# RemoteSensors.net
KiCad netlist of a schematic drawn in Altium Designer
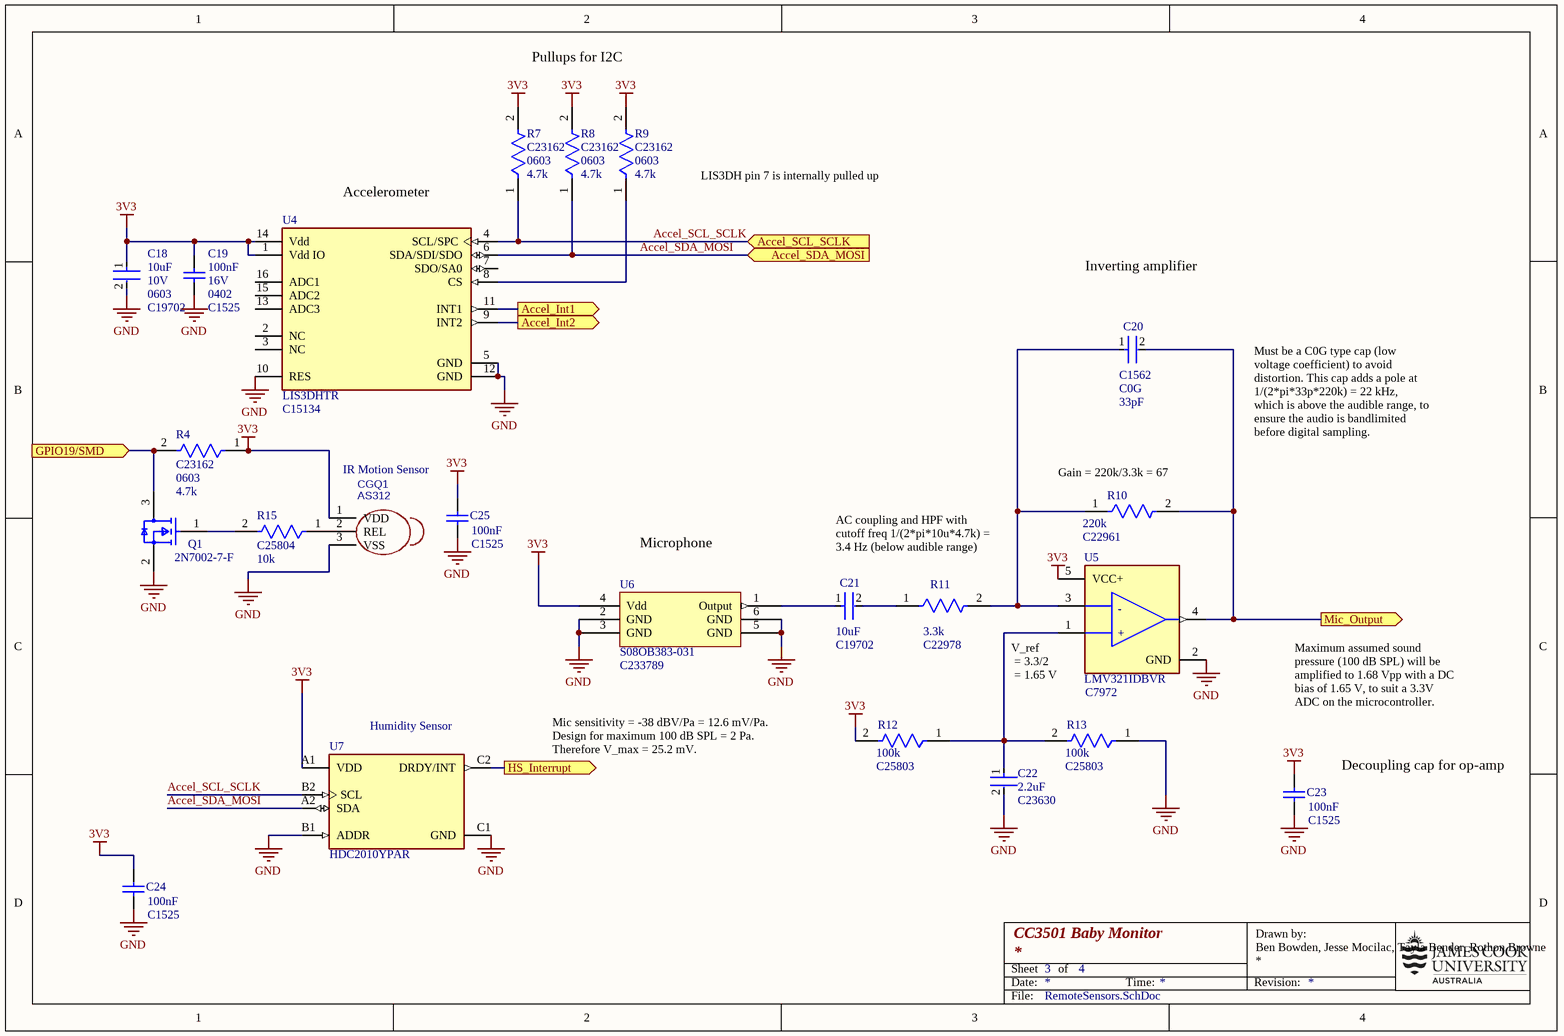
[diagram p0: RemoteSensors.SchDoc]

(export (version "E")
  (design (tool "Eeschema 10.0.6"))
  (components
    (comp (ref "C18")
      (value "CL10A106KP8NNNC")
      (footprint "FP-CL10-IPC_B")
      (description "Cap Ceramic 10uF 10V X5R ±10% Pad SMD 0603 +85°C T/R")
      (fields
        (field (name "TOLERANCE") "10%")
        (field (name "VOLTAGE RATING") "10V")
        (field (name "CASE CODE (IMPERIAL)") "0603")
        (field (name "JLCPCB PART") "C19702")
        (field (name "CAPACITANCE") "10uF")
      )
      (libsource (lib "James Cook University") (part "b4654b650e69147ec39a6b967a45e02"))
    )
    (comp (ref "C19")
      (value "CL05B104KO5NNNC")
      (footprint "CAPC1050X55X23ML05T13")
      (description "Chip Capacitor, 100 nF, +/- 10%, 16 V, -55 to 125 degC, 0402 (1005 Metric), RoHS, Tape and Reel")
      (fields
        (field (name "JLCPCB PART") "C1525")
        (field (name "CASE SIZE/DIMENSION") "0402")
        (field (name "CAPACITANCE") "100nF")
        (field (name "MANUFACTURER") "Samsung Electro-Mechanics")
        (field (name "RATED VOLTAGE") "16V")
      )
      (libsource (lib "James Cook University") (part "CAP-NP-2"))
    )
    (comp (ref "C20")
      (value "0402CG330J500NT")
      (footprint "FP-0402-L_1_0_1-W_0_5_0_1-IPC_A")
      (description "General Purpose Ceramic Capacitor, 0402, 33pF, 5%, C0G, 30ppm/°C, 50V")
      (fields
        (field (name "CAPACITANCE") "33pF")
        (field (name "DIELECTRIC") "C0G")
        (field (name "VOLTAGE") "50V")
        (field (name "JLCPCB PART") "C1562")
        (field (name "TOLERANCE") "5%")
      )
      (libsource (lib "James Cook University") (part "b4654b650e69147ec39a6b967a45e02"))
    )
    (comp (ref "C21")
      (value "CL10A106KP8NNNC")
      (footprint "FP-CL10-IPC_B")
      (description "Cap Ceramic 10uF 10V X5R ±10% Pad SMD 0603 +85°C T/R")
      (fields
        (field (name "JLCPCB PART") "C19702")
        (field (name "CAPACITANCE") "10uF")
        (field (name "TOLERANCE") "10%")
      )
      (libsource (lib "James Cook University") (part "b4654b650e69147ec39a6b967a45e02"))
    )
    (comp (ref "C22")
      (value "CL10A225KO8NNNC")
      (footprint "FP-CL10-IPC_B")
      (description "Cap Ceramic 2.2uF 16V X5R ±20% Pad SMD 0603 +85°C T/R")
      (fields
        (field (name "CAPACITANCE") "2.2uF")
        (field (name "TOLERANCE") "10%")
        (field (name "JLCPCB PART") "C23630")
      )
      (libsource (lib "James Cook University") (part "b4654b650e69147ec39a6b967a45e02"))
    )
    (comp (ref "C23")
      (value "CL05B104KO5NNNC")
      (footprint "CAPC1050X55X23ML05T13")
      (description "Chip Capacitor, 100 nF, +/- 10%, 16 V, -55 to 125 degC, 0402 (1005 Metric), RoHS, Tape and Reel")
      (fields
        (field (name "JLCPCB PART") "C1525")
        (field (name "CAPACITANCE") "100nF")
        (field (name "MANUFACTURER") "Samsung Electro-Mechanics")
      )
      (libsource (lib "James Cook University") (part "CAP-NP-2"))
    )
    (comp (ref "C24")
      (value "CL05B104KO5NNNC")
      (footprint "CAPC1050X55X23ML05T13")
      (description "Chip Capacitor, 100 nF, +/- 10%, 16 V, -55 to 125 degC, 0402 (1005 Metric), RoHS, Tape and Reel")
      (fields
        (field (name "JLCPCB PART") "C1525")
        (field (name "CAPACITANCE") "100nF")
        (field (name "MANUFACTURER") "Samsung Electro-Mechanics")
      )
      (libsource (lib "James Cook University") (part "CAP-NP-2"))
    )
    (comp (ref "C25")
      (value "CL05B104KO5NNNC")
      (footprint "CAPC1050X55X23ML05T13")
      (description "Chip Capacitor, 100 nF, +/- 10%, 16 V, -55 to 125 degC, 0402 (1005 Metric), RoHS, Tape and Reel")
      (fields
        (field (name "JLCPCB PART") "C1525")
        (field (name "CAPACITANCE") "100nF")
        (field (name "MANUFACTURER") "Samsung Electro-Mechanics")
      )
      (libsource (lib "James Cook University") (part "CAP-NP-2"))
    )
    (comp (ref "CGQ1")
      (value "AS312")
      (footprint "SENSORM-TH_3P_AS312")
      (fields (field (name "MANUFACTURER") "森霸"))
      (libsource (lib "altium-import") (part "root_0_AS312_"))
    )
    (comp (ref "Q1")
      (value "2N7002-7-F")
      (footprint "FP-SOT23-MFG")
      (description "MOSFET N-CH 60V 115MA SOT23-3")
      (fields (field (name "VOLTAGE") "60V"))
      (libsource (lib "Altium Content Vault") (part "3b9c635fedb024a5347a57b145af9cc"))
    )
    (comp (ref "R4")
      (value "0603WAF4701T5E")
      (footprint "FP-CRCW0603-e3-IPC_B")
      (description "RES Thick Film, 4.7kΩ, 1%, 0.1W, 100ppm/°C, 0603")
      (fields
        (field (name "JLCPCB PART") "C23162")
        (field (name "CASE/PACKAGE") "0603")
        (field (name "RESISTANCE") "4.7k")
        (field (name "TOLERANCE") "1%")
      )
      (libsource (lib "James Cook University") (part "1029c3af85768c4190bb7ad29bc67b5"))
    )
    (comp (ref "R7")
      (value "0603WAF4701T5E")
      (footprint "FP-CRCW0603-e3-IPC_B")
      (description "RES Thick Film, 4.7kΩ, 1%, 0.1W, 100ppm/°C, 0603")
      (fields
        (field (name "JLCPCB PART") "C23162")
        (field (name "CASE/PACKAGE") "0603")
        (field (name "RESISTANCE") "4.7k")
        (field (name "TOLERANCE") "1%")
      )
      (libsource (lib "James Cook University") (part "1029c3af85768c4190bb7ad29bc67b5"))
    )
    (comp (ref "R8")
      (value "0603WAF4701T5E")
      (footprint "FP-CRCW0603-e3-IPC_B")
      (description "RES Thick Film, 4.7kΩ, 1%, 0.1W, 100ppm/°C, 0603")
      (fields
        (field (name "JLCPCB PART") "C23162")
        (field (name "CASE/PACKAGE") "0603")
        (field (name "RESISTANCE") "4.7k")
        (field (name "TOLERANCE") "1%")
      )
      (libsource (lib "James Cook University") (part "1029c3af85768c4190bb7ad29bc67b5"))
    )
    (comp (ref "R9")
      (value "0603WAF4701T5E")
      (footprint "FP-CRCW0603-e3-IPC_B")
      (description "RES Thick Film, 4.7kΩ, 1%, 0.1W, 100ppm/°C, 0603")
      (fields
        (field (name "JLCPCB PART") "C23162")
        (field (name "CASE/PACKAGE") "0603")
        (field (name "RESISTANCE") "4.7k")
        (field (name "TOLERANCE") "1%")
      )
      (libsource (lib "James Cook University") (part "1029c3af85768c4190bb7ad29bc67b5"))
    )
    (comp (ref "R10")
      (value "0603WAF2203T5E")
      (footprint "FP-CRCW0603-e3-IPC_B")
      (description "RES Thick Film, 220kΩ, 1%, 0.1W, 100ppm/°C, 0603")
      (fields
        (field (name "RESISTANCE") "220k")
        (field (name "TOLERANCE") "1%")
        (field (name "JLCPCB PART") "C22961")
      )
      (libsource (lib "James Cook University") (part "1029c3af85768c4190bb7ad29bc67b5"))
    )
    (comp (ref "R11")
      (value "0603WAF3301T5E")
      (footprint "FP-CRCW0603-e3-IPC_B")
      (description "RES Thick Film, 3.3kΩ, 1%, 0.1W, 100ppm/°C, 0603")
      (fields
        (field (name "TOLERANCE") "1%")
        (field (name "JLCPCB PART") "C22978")
        (field (name "RESISTANCE") "3.3k")
      )
      (libsource (lib "James Cook University") (part "1029c3af85768c4190bb7ad29bc67b5"))
    )
    (comp (ref "R12")
      (value "0603WAF1003T5E")
      (footprint "FP-CRCW0603-e3-IPC_B")
      (description "RES Thick Film, 100kΩ, 1%, 0.1W, 100ppm/°C, 0603")
      (fields
        (field (name "JLCPCB PART") "C25803")
        (field (name "RESISTANCE") "100k")
        (field (name "TOLERANCE") "1%")
      )
      (libsource (lib "James Cook University") (part "1029c3af85768c4190bb7ad29bc67b5"))
    )
    (comp (ref "R13")
      (value "0603WAF1003T5E")
      (footprint "FP-CRCW0603-e3-IPC_B")
      (description "RES Thick Film, 100kΩ, 1%, 0.1W, 100ppm/°C, 0603")
      (fields
        (field (name "JLCPCB PART") "C25803")
        (field (name "RESISTANCE") "100k")
        (field (name "TOLERANCE") "1%")
      )
      (libsource (lib "James Cook University") (part "1029c3af85768c4190bb7ad29bc67b5"))
    )
    (comp (ref "R15")
      (value "0603WAF1002T5E")
      (footprint "FP-CRCW0603-e3-IPC_B")
      (description "RES Thick Film, 10kΩ, 1%, 0.1W, 100ppm/°C, 0603")
      (fields
        (field (name "TOLERANCE") "1%")
        (field (name "JLCPCB PART") "C25804")
        (field (name "RESISTANCE") "10k")
      )
      (libsource (lib "James Cook University") (part "1029c3af85768c4190bb7ad29bc67b5"))
    )
    (comp (ref "U4")
      (value "LIS3DHTR")
      (footprint "FP-LGA-16-7983231-MFG")
      (description "ACCEL 2-16G I2C/SPI 16LGA")
      (fields (field (name "JLCPCB PART") "C15134"))
      (libsource (lib "James Cook University") (part "1e4772b22d749da4b53766bc623c8dd"))
    )
    (comp (ref "U5")
      (value "LMV321IDBVR")
      (footprint "FP-DBV0005A-IPC_B")
      (description "General Purpose Amplifier 1 Circuit Rail-to-Rail SOT-23-5")
      (fields (field (name "JLCPCB PART") "C7972"))
      (libsource (lib "James Cook University") (part "ec165d7f6fd2c1e6935a66fb0025aed"))
    )
    (comp (ref "U6")
      (value "S08OB383-031")
      (footprint "Goertek_S08OB381-026")
      (description "MEMS Microphone SMD 3.76x3x1.1mm")
      (fields (field (name "JLCPCB PART") "C233789"))
      (libsource (lib "James Cook University") (part "Goertek S08OB381-026"))
    )
    (comp (ref "U7")
      (value "HDC2010YPAR")
      (footprint "FP-YPA0006-MFG")
      (description "GEN 2 HUMIDITY SENSOR")
      (fields
        (field (name "MANUFACTURER") "Texas Instruments")
        (field (name "OCTOPART") "https://octopart.com/hdc2010ypar-texas+instruments-84791680")
      )
      (libsource (lib "Altium Content Vault") (part "89629a78d3446019ed046f2f7a99f7b"))
    )
  )
  (nets
    (net (code "1") (name "/Accel_Int1") (class "Default")
      (node (ref "U4") (pin "11") (pinfunction "INT1_11") (pintype "output"))
    )
    (net (code "2") (name "/Accel_Int2") (class "Default")
      (node (ref "U4") (pin "9") (pinfunction "INT2_9") (pintype "output"))
    )
    (net (code "3") (name "/Accel_SCL_SCLK") (class "Default")
      (node (ref "R7") (pin "1") (pinfunction "1_1") (pintype "passive"))
      (node (ref "U4") (pin "4") (pinfunction "SCL/SPC_4") (pintype "input"))
      (node (ref "U7") (pin "B2") (pinfunction "SCL_B2") (pintype "input"))
    )
    (net (code "4") (name "/Accel_SDA_MOSI") (class "Default")
      (node (ref "R8") (pin "1") (pinfunction "1_1") (pintype "passive"))
      (node (ref "U4") (pin "6") (pinfunction "SDA/SDI/SDO_6") (pintype "bidirectional"))
      (node (ref "U7") (pin "A2") (pinfunction "SDA_A2") (pintype "bidirectional"))
    )
    (net (code "5") (name "/GPIO19{slash}SMD") (class "Default")
      (node (ref "Q1") (pin "3") (pinfunction "D_3") (pintype "passive"))
      (node (ref "R4") (pin "2") (pinfunction "2_2") (pintype "passive"))
    )
    (net (code "6") (name "/HS_Interrupt") (class "Default")
      (node (ref "U7") (pin "C2") (pinfunction "DRDY/INT_C2") (pintype "output"))
    )
    (net (code "7") (name "/Mic_Output") (class "Default")
      (node (ref "C20") (pin "2") (pinfunction "2_2") (pintype "passive"))
      (node (ref "R10") (pin "2") (pinfunction "2_2") (pintype "passive"))
      (node (ref "U5") (pin "4") (pinfunction "OUT_4") (pintype "output"))
    )
    (net (code "8") (name "3V3") (class "Default")
      (node (ref "C18") (pin "1") (pinfunction "1_1") (pintype "passive"))
      (node (ref "C19") (pin "2") (pinfunction "2_2") (pintype "passive"))
      (node (ref "C23") (pin "2") (pinfunction "2_2") (pintype "passive"))
      (node (ref "C24") (pin "2") (pinfunction "2_2") (pintype "passive"))
      (node (ref "C25") (pin "2") (pinfunction "2_2") (pintype "passive"))
      (node (ref "CGQ1") (pin "1") (pinfunction "VDD_1") (pintype "passive"))
      (node (ref "R12") (pin "2") (pinfunction "2_2") (pintype "passive"))
      (node (ref "R4") (pin "1") (pinfunction "1_1") (pintype "passive"))
      (node (ref "R7") (pin "2") (pinfunction "2_2") (pintype "passive"))
      (node (ref "R8") (pin "2") (pinfunction "2_2") (pintype "passive"))
      (node (ref "R9") (pin "2") (pinfunction "2_2") (pintype "passive"))
      (node (ref "U4") (pin "1") (pinfunction "Vdd_IO_1") (pintype "power_in"))
      (node (ref "U4") (pin "14") (pinfunction "Vdd_14") (pintype "power_in"))
      (node (ref "U5") (pin "5") (pinfunction "VCC+_5") (pintype "power_in"))
      (node (ref "U6") (pin "4") (pinfunction "Vdd_4") (pintype "power_in"))
      (node (ref "U7") (pin "A1") (pinfunction "VDD_A1") (pintype "power_in"))
    )
    (net (code "9") (name "GND") (class "Default")
      (node (ref "C18") (pin "2") (pinfunction "2_2") (pintype "passive"))
      (node (ref "C19") (pin "1") (pinfunction "1_1") (pintype "passive"))
      (node (ref "C22") (pin "2") (pinfunction "2_2") (pintype "passive"))
      (node (ref "C23") (pin "1") (pinfunction "1_1") (pintype "passive"))
      (node (ref "C24") (pin "1") (pinfunction "1_1") (pintype "passive"))
      (node (ref "C25") (pin "1") (pinfunction "1_1") (pintype "passive"))
      (node (ref "CGQ1") (pin "3") (pinfunction "VSS_3") (pintype "passive"))
      (node (ref "Q1") (pin "2") (pinfunction "S_2") (pintype "passive"))
      (node (ref "R13") (pin "1") (pinfunction "1_1") (pintype "passive"))
      (node (ref "U4") (pin "10") (pinfunction "RES_10") (pintype "passive"))
      (node (ref "U4") (pin "12") (pinfunction "GND_12") (pintype "power_in"))
      (node (ref "U4") (pin "5") (pinfunction "GND_5") (pintype "power_in"))
      (node (ref "U5") (pin "2") (pinfunction "GND_2") (pintype "power_in"))
      (node (ref "U6") (pin "2") (pinfunction "GND_2") (pintype "power_in"))
      (node (ref "U6") (pin "3") (pinfunction "GND_3") (pintype "power_in"))
      (node (ref "U6") (pin "5") (pinfunction "GND_5") (pintype "power_in"))
      (node (ref "U6") (pin "6") (pinfunction "GND_6") (pintype "power_in"))
      (node (ref "U7") (pin "B1") (pinfunction "ADDR_B1") (pintype "input"))
      (node (ref "U7") (pin "C1") (pinfunction "GND_C1") (pintype "power_in"))
    )
    (net (code "10") (name "Net-(C21-Pad2)") (class "Default")
      (node (ref "C21") (pin "2") (pinfunction "2_2") (pintype "passive"))
      (node (ref "R11") (pin "1") (pinfunction "1_1") (pintype "passive"))
    )
    (net (code "11") (name "Net-(CGQ1-REL)") (class "Default")
      (node (ref "CGQ1") (pin "2") (pinfunction "REL_2") (pintype "passive"))
      (node (ref "R15") (pin "1") (pinfunction "1_1") (pintype "passive"))
    )
    (net (code "12") (name "Net-(Q1-G)") (class "Default")
      (node (ref "Q1") (pin "1") (pinfunction "G_1") (pintype "passive"))
      (node (ref "R15") (pin "2") (pinfunction "2_2") (pintype "passive"))
    )
    (net (code "13") (name "Net-(U4-CS)") (class "Default")
      (node (ref "R9") (pin "1") (pinfunction "1_1") (pintype "passive"))
      (node (ref "U4") (pin "8") (pinfunction "CS_8") (pintype "input"))
    )
    (net (code "14") (name "Net-(U5-1IN+)") (class "Default")
      (node (ref "C22") (pin "1") (pinfunction "1_1") (pintype "passive"))
      (node (ref "R12") (pin "1") (pinfunction "1_1") (pintype "passive"))
      (node (ref "R13") (pin "2") (pinfunction "2_2") (pintype "passive"))
      (node (ref "U5") (pin "1") (pinfunction "1IN+_1") (pintype "tri_state"))
    )
    (net (code "15") (name "Net-(U5-1IN-)") (class "Default")
      (node (ref "C20") (pin "1") (pinfunction "1_1") (pintype "passive"))
      (node (ref "R10") (pin "1") (pinfunction "1_1") (pintype "passive"))
      (node (ref "R11") (pin "2") (pinfunction "2_2") (pintype "passive"))
      (node (ref "U5") (pin "3") (pinfunction "1IN-_3") (pintype "tri_state"))
    )
    (net (code "16") (name "Net-(U6-Output)") (class "Default")
      (node (ref "C21") (pin "1") (pinfunction "1_1") (pintype "passive"))
      (node (ref "U6") (pin "1") (pinfunction "Output_1") (pintype "output"))
    )
    (net (code "17") (name "unconnected-(U4-ADC1-Pad16)") (class "Default")
      (node (ref "U4") (pin "16") (pinfunction "ADC1_16") (pintype "passive"))
    )
    (net (code "18") (name "unconnected-(U4-ADC2-Pad15)") (class "Default")
      (node (ref "U4") (pin "15") (pinfunction "ADC2_15") (pintype "passive"))
    )
    (net (code "19") (name "unconnected-(U4-ADC3-Pad13)") (class "Default")
      (node (ref "U4") (pin "13") (pinfunction "ADC3_13") (pintype "passive"))
    )
    (net (code "20") (name "unconnected-(U4-NC-Pad2)") (class "Default")
      (node (ref "U4") (pin "2") (pinfunction "NC_2") (pintype "passive"))
    )
    (net (code "21") (name "unconnected-(U4-NC-Pad3)") (class "Default")
      (node (ref "U4") (pin "3") (pinfunction "NC_3") (pintype "passive"))
    )
    (net (code "22") (name "unconnected-(U4-SDO{slash}SA0-Pad7)") (class "Default")
      (node (ref "U4") (pin "7") (pinfunction "SDO/SA0_7") (pintype "bidirectional"))
    )
  )
)
